# SectionC_BreakOut.net
KiCad netlist of a schematic drawn in Altium Designer
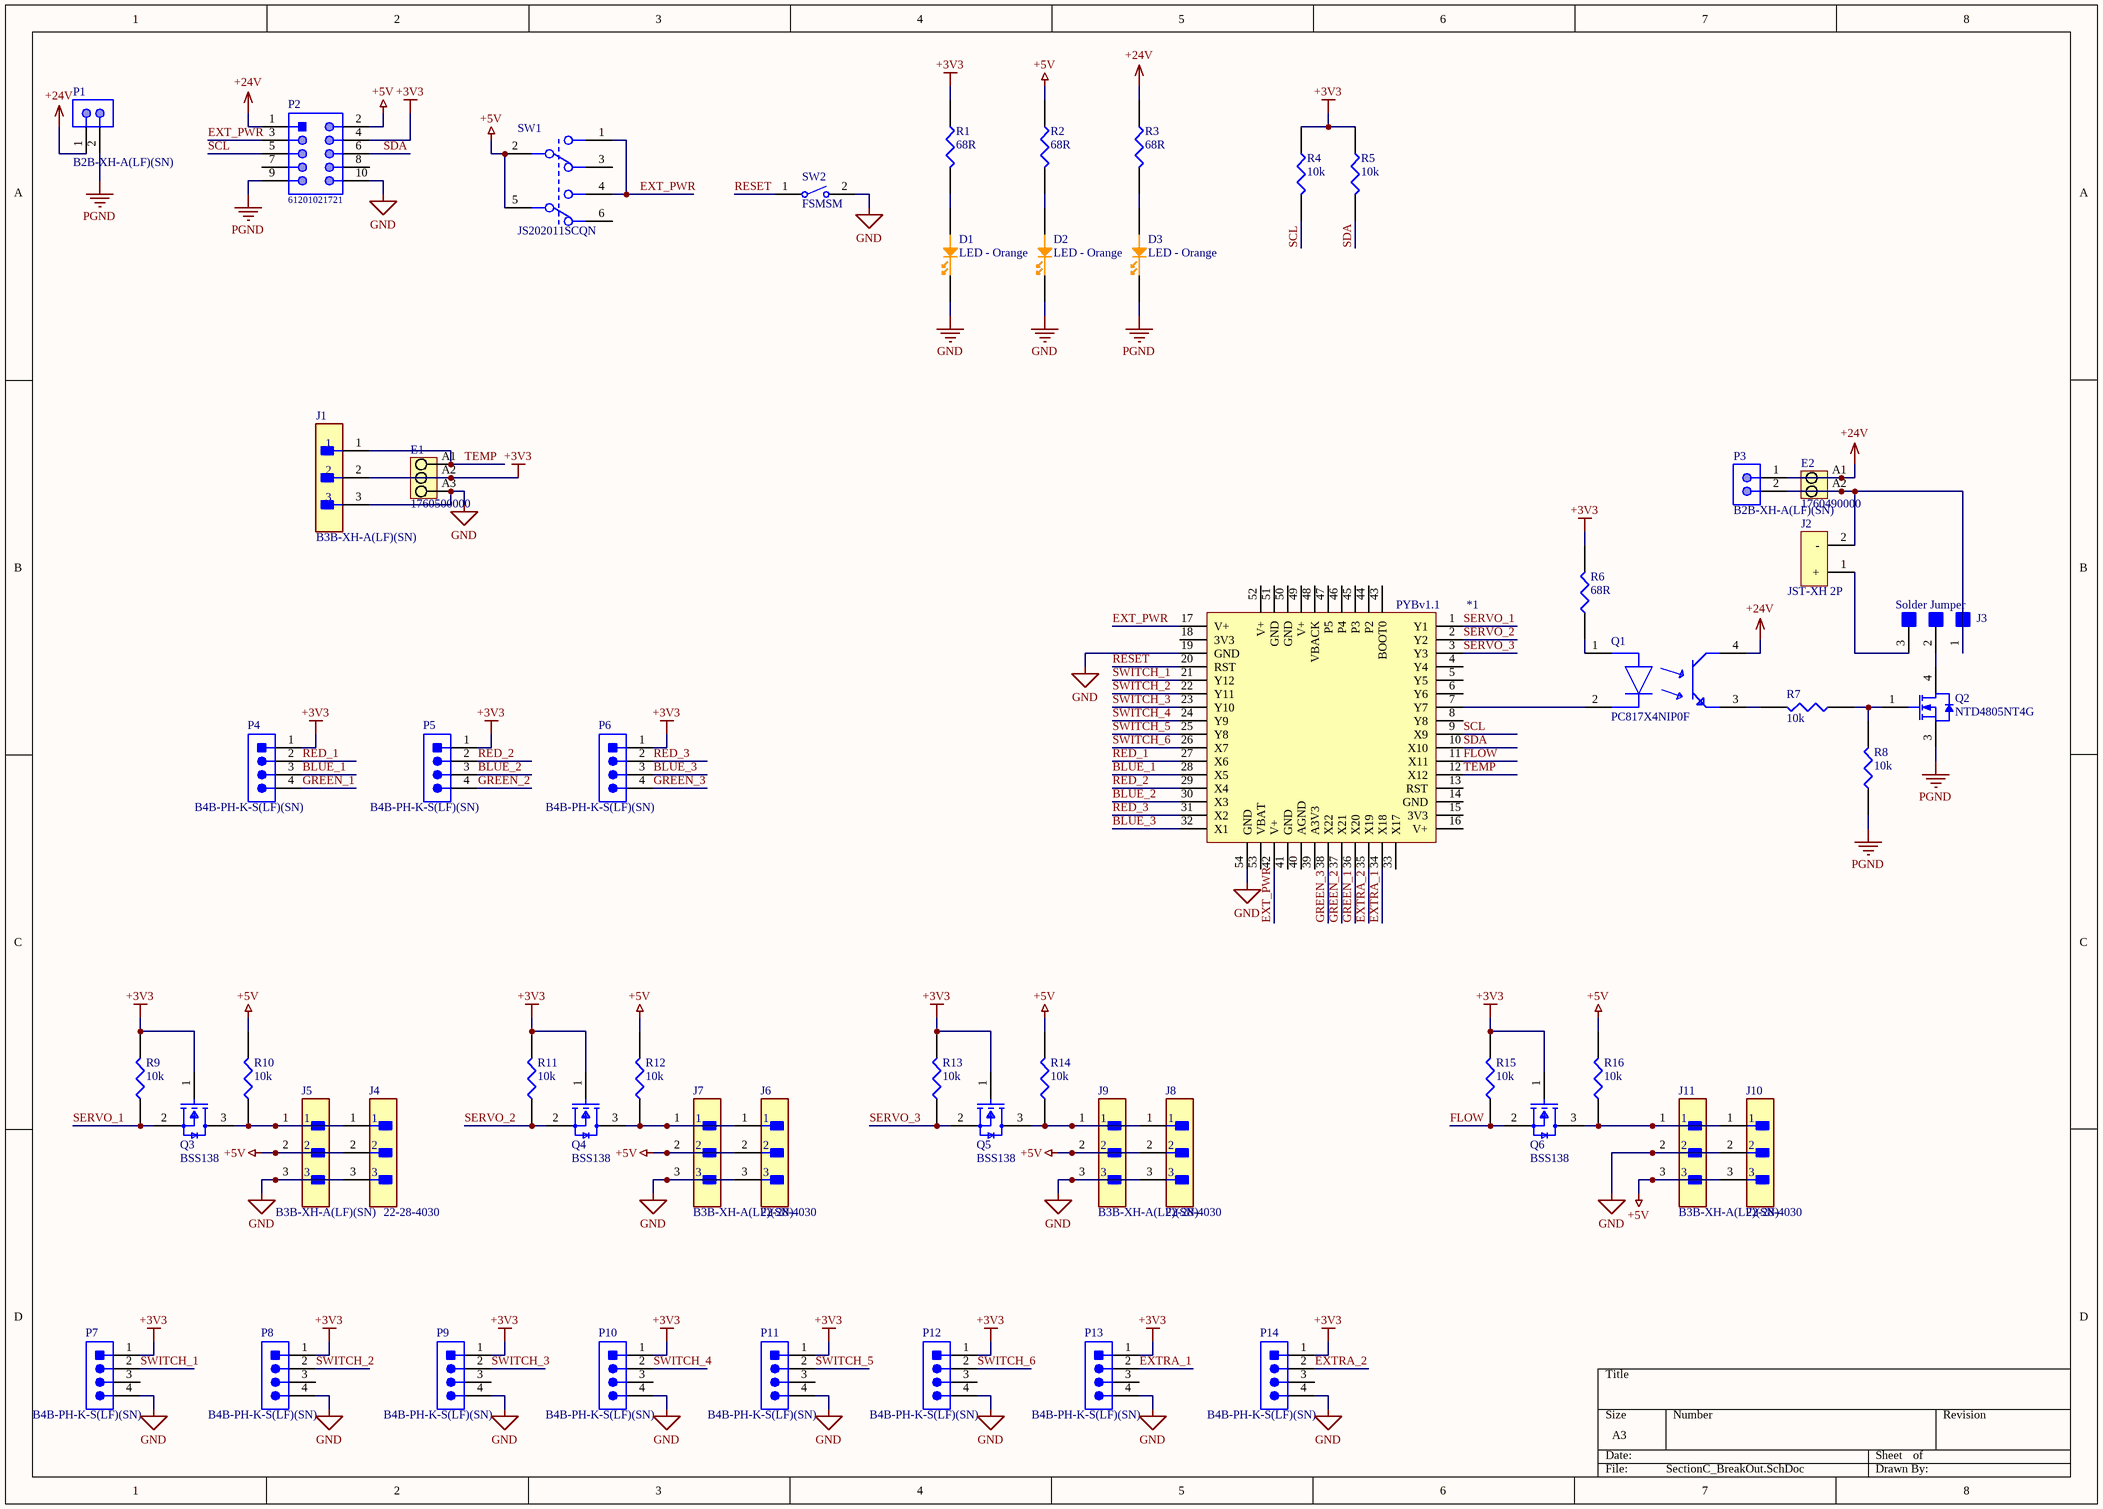
[diagram p0: SectionC_BreakOut.SchDoc]

(export (version "E")
  (design (tool "Eeschema 10.0.6"))
  (components
    (comp (ref "*1")
      (value "PYBv1.1")
      (footprint "PYBv1.1")
      (libsource (lib "SectionC_BreakOut") (part "PYBv1.1"))
    )
    (comp (ref "D1")
      (value "LED - Orange")
      (footprint "LED0603-Orange")
      (description "LED ORANGE CLEAR SMD")
      (fields
        (field (name "MANUFACTURER") "Vishay Lite-On")
        (field (name "MANUFACTURER PART NUMBER") "LTST-C191KFKT")
      )
      (libsource (lib "Limit_Switch_RGB") (part "LTST-C191KFKT"))
    )
    (comp (ref "D2")
      (value "LED - Orange")
      (footprint "LED0603-Orange")
      (description "LED ORANGE CLEAR SMD")
      (fields
        (field (name "MANUFACTURER") "Vishay Lite-On")
        (field (name "MANUFACTURER PART NUMBER") "LTST-C191KFKT")
      )
      (libsource (lib "Limit_Switch_RGB") (part "LTST-C191KFKT"))
    )
    (comp (ref "D3")
      (value "LED - Orange")
      (footprint "LED0603-Orange")
      (description "LED ORANGE CLEAR SMD")
      (fields
        (field (name "MANUFACTURER") "Vishay Lite-On")
        (field (name "MANUFACTURER PART NUMBER") "LTST-C191KFKT")
      )
      (libsource (lib "Limit_Switch_RGB") (part "LTST-C191KFKT"))
    )
    (comp (ref "E1")
      (value "1760500000")
      (footprint "PM_5_08_90_03")
      (description "OMNIMATE Signal - series PM")
      (fields (field (name "MANUFACTURER") "Weidmueller"))
      (libsource (lib "Altium Content Vault") (part "Terminal_03_1x03"))
    )
    (comp (ref "E2")
      (value "1760490000")
      (footprint "PM_5_08_90_02")
      (description "OMNIMATE Signal - series PM")
      (fields (field (name "MANUFACTURER") "Weidmueller"))
      (libsource (lib "Altium Content Vault") (part "Terminal_02_1x02"))
    )
    (comp (ref "J1")
      (value "B3B-XH-A(LF)(SN)")
      (footprint "FP-B3B-XH-A_LF_SN-MFG")
      (description "CONN HEADER VERT 3POS 2.5MM")
      (fields
        (field (name "OCTOPART") "https://octopart.com/b3b-xh-a%28lf%29%28sn%29-jst-3990185")
        (field (name "MANUFACTURER") "JST")
      )
      (libsource (lib "") (part "0d3f023dd272f625e17a2be33dea85f_1"))
    )
    (comp (ref "J2")
      (value "JST-XH 2P")
      (footprint "JST-XH 2P")
      (description "JST-XH 2 POS 2.5mm Solder ST Thru-Hole Box")
      (fields
        (field (name "MANUFACTURER") "JST")
        (field (name "MANUFACTURER PART NUMBER") "B2B-XH-A(LF)(SN)")
      )
      (libsource (lib "SectionE_BreakOut") (part "B2B-XH-A(LF)(SN)"))
    )
    (comp (ref "J3")
      (value "Solder Jumper")
      (footprint "Solder Jumper")
      (libsource (lib "SectionE_BreakOut") (part "Solder Jumper"))
    )
    (comp (ref "J4")
      (value "22-28-4030")
      (footprint "FP-22-28-4030-MFG")
      (description "CONN HEADER VERT 3POS 2.54MM")
      (fields
        (field (name "OCTOPART") "https://octopart.com/0022284030-molex-10476094")
        (field (name "MANUFACTURER") "Molex")
      )
      (libsource (lib "Altium Content Vault") (part "0d3f023dd272f625e17a2be33dea85f"))
    )
    (comp (ref "J5")
      (value "B3B-XH-A(LF)(SN)")
      (footprint "FP-B3B-XH-A_LF_SN-MFG")
      (description "CONN HEADER VERT 3POS 2.5MM")
      (fields
        (field (name "OCTOPART") "https://octopart.com/b3b-xh-a%28lf%29%28sn%29-jst-3990185")
        (field (name "MANUFACTURER") "JST")
      )
      (libsource (lib "Altium Content Vault") (part "0d3f023dd272f625e17a2be33dea85f"))
    )
    (comp (ref "J6")
      (value "22-28-4030")
      (footprint "FP-22-28-4030-MFG")
      (description "CONN HEADER VERT 3POS 2.54MM")
      (fields
        (field (name "OCTOPART") "https://octopart.com/0022284030-molex-10476094")
        (field (name "MANUFACTURER") "Molex")
      )
      (libsource (lib "Altium Content Vault") (part "0d3f023dd272f625e17a2be33dea85f"))
    )
    (comp (ref "J7")
      (value "B3B-XH-A(LF)(SN)")
      (footprint "FP-B3B-XH-A_LF_SN-MFG")
      (description "CONN HEADER VERT 3POS 2.5MM")
      (fields
        (field (name "OCTOPART") "https://octopart.com/b3b-xh-a%28lf%29%28sn%29-jst-3990185")
        (field (name "MANUFACTURER") "JST")
      )
      (libsource (lib "Altium Content Vault") (part "0d3f023dd272f625e17a2be33dea85f"))
    )
    (comp (ref "J8")
      (value "22-28-4030")
      (footprint "FP-22-28-4030-MFG")
      (description "CONN HEADER VERT 3POS 2.54MM")
      (fields
        (field (name "OCTOPART") "https://octopart.com/0022284030-molex-10476094")
        (field (name "MANUFACTURER") "Molex")
      )
      (libsource (lib "Altium Content Vault") (part "0d3f023dd272f625e17a2be33dea85f"))
    )
    (comp (ref "J9")
      (value "B3B-XH-A(LF)(SN)")
      (footprint "FP-B3B-XH-A_LF_SN-MFG")
      (description "CONN HEADER VERT 3POS 2.5MM")
      (fields
        (field (name "OCTOPART") "https://octopart.com/b3b-xh-a%28lf%29%28sn%29-jst-3990185")
        (field (name "MANUFACTURER") "JST")
      )
      (libsource (lib "Altium Content Vault") (part "0d3f023dd272f625e17a2be33dea85f"))
    )
    (comp (ref "J10")
      (value "22-28-4030")
      (footprint "FP-22-28-4030-MFG")
      (description "CONN HEADER VERT 3POS 2.54MM")
      (fields
        (field (name "OCTOPART") "https://octopart.com/0022284030-molex-10476094")
        (field (name "MANUFACTURER") "Molex")
      )
      (libsource (lib "Altium Content Vault") (part "0d3f023dd272f625e17a2be33dea85f"))
    )
    (comp (ref "J11")
      (value "B3B-XH-A(LF)(SN)")
      (footprint "FP-B3B-XH-A_LF_SN-MFG")
      (description "CONN HEADER VERT 3POS 2.5MM")
      (fields
        (field (name "OCTOPART") "https://octopart.com/b3b-xh-a%28lf%29%28sn%29-jst-3990185")
        (field (name "MANUFACTURER") "JST")
      )
      (libsource (lib "Altium Content Vault") (part "0d3f023dd272f625e17a2be33dea85f"))
    )
    (comp (ref "P1")
      (value "B2B-XH-A(LF)(SN)")
      (footprint "JST-B2B-XH-A_V")
      (fields (field (name "MANUFACTURER") "JST"))
      (libsource (lib "Altium Content Vault") (part "CN-1P-M-R2"))
    )
    (comp (ref "P2")
      (value "61201021721")
      (footprint "61201021721")
      (description "Male Box Header WR-BHD, THT, Angled, pitch 2.54 mm, 10 pins")
      (fields (field (name "MANUFACTURER") "Wurth Elektronik") (field (name "PUBLISHER") "WurthElektronik"))
      (libsource (lib "Altium Content Vault") (part "WE-CN-2P-M-R10"))
    )
    (comp (ref "P3")
      (value "B2B-XH-A(LF)(SN)")
      (footprint "JST-B2B-XH-A_V")
      (fields (field (name "MANUFACTURER") "JST"))
      (libsource (lib "") (part "CN-1P-M-R2_1"))
    )
    (comp (ref "P4")
      (value "B4B-PH-K-S(LF)(SN)")
      (footprint "JST-B4B-PH-K-S_V")
      (fields (field (name "MANUFACTURER") "JST"))
      (libsource (lib "Altium Content Vault") (part "CN-1P-M-R4"))
    )
    (comp (ref "P5")
      (value "B4B-PH-K-S(LF)(SN)")
      (footprint "JST-B4B-PH-K-S_V")
      (fields (field (name "MANUFACTURER") "JST"))
      (libsource (lib "Altium Content Vault") (part "CN-1P-M-R4"))
    )
    (comp (ref "P6")
      (value "B4B-PH-K-S(LF)(SN)")
      (footprint "JST-B4B-PH-K-S_V")
      (fields (field (name "MANUFACTURER") "JST"))
      (libsource (lib "Altium Content Vault") (part "CN-1P-M-R4"))
    )
    (comp (ref "P7")
      (value "B4B-PH-K-S(LF)(SN)")
      (footprint "JST-B4B-PH-K-S_V")
      (fields (field (name "MANUFACTURER") "JST"))
      (libsource (lib "Altium Content Vault") (part "CN-1P-M-R4"))
    )
    (comp (ref "P8")
      (value "B4B-PH-K-S(LF)(SN)")
      (footprint "JST-B4B-PH-K-S_V")
      (fields (field (name "MANUFACTURER") "JST"))
      (libsource (lib "Altium Content Vault") (part "CN-1P-M-R4"))
    )
    (comp (ref "P9")
      (value "B4B-PH-K-S(LF)(SN)")
      (footprint "JST-B4B-PH-K-S_V")
      (fields (field (name "MANUFACTURER") "JST"))
      (libsource (lib "Altium Content Vault") (part "CN-1P-M-R4"))
    )
    (comp (ref "P10")
      (value "B4B-PH-K-S(LF)(SN)")
      (footprint "JST-B4B-PH-K-S_V")
      (fields (field (name "MANUFACTURER") "JST"))
      (libsource (lib "Altium Content Vault") (part "CN-1P-M-R4"))
    )
    (comp (ref "P11")
      (value "B4B-PH-K-S(LF)(SN)")
      (footprint "JST-B4B-PH-K-S_V")
      (fields (field (name "MANUFACTURER") "JST"))
      (libsource (lib "Altium Content Vault") (part "CN-1P-M-R4"))
    )
    (comp (ref "P12")
      (value "B4B-PH-K-S(LF)(SN)")
      (footprint "JST-B4B-PH-K-S_V")
      (fields (field (name "MANUFACTURER") "JST"))
      (libsource (lib "Altium Content Vault") (part "CN-1P-M-R4"))
    )
    (comp (ref "P13")
      (value "B4B-PH-K-S(LF)(SN)")
      (footprint "JST-B4B-PH-K-S_V")
      (fields (field (name "MANUFACTURER") "JST"))
      (libsource (lib "Altium Content Vault") (part "CN-1P-M-R4"))
    )
    (comp (ref "P14")
      (value "B4B-PH-K-S(LF)(SN)")
      (footprint "JST-B4B-PH-K-S_V")
      (fields (field (name "MANUFACTURER") "JST"))
      (libsource (lib "Altium Content Vault") (part "CN-1P-M-R4"))
    )
    (comp (ref "Q1")
      (value "PC817X4NIP0F")
      (footprint "FP-PC817X4NIP0F-MFG")
      (description "OPTOISOLATOR 5KV TRANS 4SMD")
      (fields
        (field (name "OCTOPART") "https://octopart.com/pc817x4nip0f-sharp-20650453")
        (field (name "MANUFACTURER") "Sharp")
      )
      (libsource (lib "Altium Content Vault") (part "8ff5844b63c0dea0057760e9ee25456"))
    )
    (comp (ref "Q2")
      (value "NTD4805NT4G")
      (footprint "ONSC-DPAK-3-369AA-01_V")
      (description "Power MOSFET, 30 V, 88 A, Single N-Channel, 3-Pin DPAK, Pb-Free, Tape and Reel")
      (fields (field (name "MANUFACTURER") "On Semiconductor"))
      (libsource (lib "Altium Content Vault") (part "ONSC-NMOS-G1S3D4-3_B"))
    )
    (comp (ref "Q3")
      (value "BSS138")
      (footprint "FP-318-08-IPC_B")
      (description "MOSFET N-CH 50V 220MA SOT-23")
      (libsource (lib "Altium Content Vault") (part "3b9c635fedb024a5347a57b145af9cc"))
    )
    (comp (ref "Q4")
      (value "BSS138")
      (footprint "FP-318-08-IPC_B")
      (description "MOSFET N-CH 50V 220MA SOT-23")
      (libsource (lib "Altium Content Vault") (part "3b9c635fedb024a5347a57b145af9cc"))
    )
    (comp (ref "Q5")
      (value "BSS138")
      (footprint "FP-318-08-IPC_B")
      (description "MOSFET N-CH 50V 220MA SOT-23")
      (libsource (lib "Altium Content Vault") (part "3b9c635fedb024a5347a57b145af9cc"))
    )
    (comp (ref "Q6")
      (value "BSS138")
      (footprint "FP-318-08-IPC_B")
      (description "MOSFET N-CH 50V 220MA SOT-23")
      (libsource (lib "Altium Content Vault") (part "3b9c635fedb024a5347a57b145af9cc"))
    )
    (comp (ref "R1")
      (value "68R")
      (footprint "68R 0603")
      (description "CRGP 0603 68R 1%")
      (fields
        (field (name "MANUFACTURER") "TE Connectivity")
        (field (name "MANUFACTURER PART NUMBER") "CRGP0603F68R")
      )
      (libsource (lib "Limit_Switch_RGB") (part "CRGP0603F68R"))
    )
    (comp (ref "R2")
      (value "68R")
      (footprint "68R 0603")
      (description "CRGP 0603 68R 1%")
      (fields
        (field (name "MANUFACTURER") "TE Connectivity")
        (field (name "MANUFACTURER PART NUMBER") "CRGP0603F68R")
      )
      (libsource (lib "Limit_Switch_RGB") (part "CRGP0603F68R"))
    )
    (comp (ref "R3")
      (value "68R")
      (footprint "68R 0603")
      (description "CRGP 0603 68R 1%")
      (fields
        (field (name "MANUFACTURER") "TE Connectivity")
        (field (name "MANUFACTURER PART NUMBER") "CRGP0603F68R")
      )
      (libsource (lib "Limit_Switch_RGB") (part "CRGP0603F68R"))
    )
    (comp (ref "R4")
      (value "10k")
      (footprint "10k R0603")
      (description "RES 10.0K OHM 1/10W 1% 0603")
      (fields
        (field (name "MANUFACTURER") "TE Connectivity")
        (field (name "MANUFACTURER PART NUMBER") "CRG0603F10K/10")
      )
      (libsource (lib "Limit_Switch_RGB") (part "CRG0603F10K/10"))
    )
    (comp (ref "R5")
      (value "10k")
      (footprint "10k R0603")
      (description "RES 10.0K OHM 1/10W 1% 0603")
      (fields
        (field (name "MANUFACTURER") "TE Connectivity")
        (field (name "MANUFACTURER PART NUMBER") "CRG0603F10K/10")
      )
      (libsource (lib "Limit_Switch_RGB") (part "CRG0603F10K/10"))
    )
    (comp (ref "R6")
      (value "68R")
      (footprint "68R 0603")
      (description "CRGP 0603 68R 1%")
      (fields
        (field (name "MANUFACTURER") "TE Connectivity")
        (field (name "MANUFACTURER PART NUMBER") "CRGP0603F68R")
      )
      (libsource (lib "Limit_Switch_RGB") (part "CRGP0603F68R"))
    )
    (comp (ref "R7")
      (value "10k")
      (footprint "10k R0603")
      (description "RES 10.0K OHM 1/10W 1% 0603")
      (fields
        (field (name "MANUFACTURER") "TE Connectivity")
        (field (name "MANUFACTURER PART NUMBER") "CRG0603F10K/10")
      )
      (libsource (lib "Limit_Switch_RGB") (part "CRG0603F10K/10"))
    )
    (comp (ref "R8")
      (value "10k")
      (footprint "10k R0603")
      (description "RES 10.0K OHM 1/10W 1% 0603")
      (fields
        (field (name "MANUFACTURER") "TE Connectivity")
        (field (name "MANUFACTURER PART NUMBER") "CRG0603F10K/10")
      )
      (libsource (lib "Limit_Switch_RGB") (part "CRG0603F10K/10"))
    )
    (comp (ref "R9")
      (value "10k")
      (footprint "10k R0603")
      (description "RES 10.0K OHM 1/10W 1% 0603")
      (fields
        (field (name "MANUFACTURER") "TE Connectivity")
        (field (name "MANUFACTURER PART NUMBER") "CRG0603F10K/10")
      )
      (libsource (lib "Limit_Switch_RGB") (part "CRG0603F10K/10"))
    )
    (comp (ref "R10")
      (value "10k")
      (footprint "10k R0603")
      (description "RES 10.0K OHM 1/10W 1% 0603")
      (fields
        (field (name "MANUFACTURER") "TE Connectivity")
        (field (name "MANUFACTURER PART NUMBER") "CRG0603F10K/10")
      )
      (libsource (lib "Limit_Switch_RGB") (part "CRG0603F10K/10"))
    )
    (comp (ref "R11")
      (value "10k")
      (footprint "10k R0603")
      (description "RES 10.0K OHM 1/10W 1% 0603")
      (fields
        (field (name "MANUFACTURER") "TE Connectivity")
        (field (name "MANUFACTURER PART NUMBER") "CRG0603F10K/10")
      )
      (libsource (lib "Limit_Switch_RGB") (part "CRG0603F10K/10"))
    )
    (comp (ref "R12")
      (value "10k")
      (footprint "10k R0603")
      (description "RES 10.0K OHM 1/10W 1% 0603")
      (fields
        (field (name "MANUFACTURER") "TE Connectivity")
        (field (name "MANUFACTURER PART NUMBER") "CRG0603F10K/10")
      )
      (libsource (lib "Limit_Switch_RGB") (part "CRG0603F10K/10"))
    )
    (comp (ref "R13")
      (value "10k")
      (footprint "10k R0603")
      (description "RES 10.0K OHM 1/10W 1% 0603")
      (fields
        (field (name "MANUFACTURER") "TE Connectivity")
        (field (name "MANUFACTURER PART NUMBER") "CRG0603F10K/10")
      )
      (libsource (lib "Limit_Switch_RGB") (part "CRG0603F10K/10"))
    )
    (comp (ref "R14")
      (value "10k")
      (footprint "10k R0603")
      (description "RES 10.0K OHM 1/10W 1% 0603")
      (fields
        (field (name "MANUFACTURER") "TE Connectivity")
        (field (name "MANUFACTURER PART NUMBER") "CRG0603F10K/10")
      )
      (libsource (lib "Limit_Switch_RGB") (part "CRG0603F10K/10"))
    )
    (comp (ref "R15")
      (value "10k")
      (footprint "10k R0603")
      (description "RES 10.0K OHM 1/10W 1% 0603")
      (fields
        (field (name "MANUFACTURER") "TE Connectivity")
        (field (name "MANUFACTURER PART NUMBER") "CRG0603F10K/10")
      )
      (libsource (lib "Limit_Switch_RGB") (part "CRG0603F10K/10"))
    )
    (comp (ref "R16")
      (value "10k")
      (footprint "10k R0603")
      (description "RES 10.0K OHM 1/10W 1% 0603")
      (fields
        (field (name "MANUFACTURER") "TE Connectivity")
        (field (name "MANUFACTURER PART NUMBER") "CRG0603F10K/10")
      )
      (libsource (lib "Limit_Switch_RGB") (part "CRG0603F10K/10"))
    )
    (comp (ref "SW1")
      (value "JS202011SCQN")
      (footprint "FP-JS202011SCQN-MFG")
      (description "SWITCH SLIDE DPDT 300MA 6V")
      (libsource (lib "Altium Content Vault") (part "ac99ea1af431c19115f5225061c5c88"))
    )
    (comp (ref "SW2")
      (value "FSMSM")
      (footprint "TECO-FSMSM-2_V")
      (description "FSMSM Push Button Switch, 50 mA, -35 to 85 degC, 2-Pin SMD, RoHS, Bulk")
      (fields (field (name "MANUFACTURER") "TE Connectivity"))
      (libsource (lib "Altium Content Vault") (part "SW-SPST-2_C"))
    )
  )
  (nets
    (net (code "1") (name "+3V3") (class "Default")
      (node (ref "E1") (pin "A2") (pinfunction "A2_A2") (pintype "passive"))
      (node (ref "J1") (pin "2") (pinfunction "2_2") (pintype "passive"))
      (node (ref "P10") (pin "1") (pinfunction "1_1") (pintype "passive"))
      (node (ref "P11") (pin "1") (pinfunction "1_1") (pintype "passive"))
      (node (ref "P12") (pin "1") (pinfunction "1_1") (pintype "passive"))
      (node (ref "P13") (pin "1") (pinfunction "1_1") (pintype "passive"))
      (node (ref "P14") (pin "1") (pinfunction "1_1") (pintype "passive"))
      (node (ref "P2") (pin "4") (pinfunction "4_4") (pintype "passive"))
      (node (ref "P4") (pin "1") (pinfunction "1_1") (pintype "passive"))
      (node (ref "P5") (pin "1") (pinfunction "1_1") (pintype "passive"))
      (node (ref "P6") (pin "1") (pinfunction "1_1") (pintype "passive"))
      (node (ref "P7") (pin "1") (pinfunction "1_1") (pintype "passive"))
      (node (ref "P8") (pin "1") (pinfunction "1_1") (pintype "passive"))
      (node (ref "P9") (pin "1") (pinfunction "1_1") (pintype "passive"))
      (node (ref "Q3") (pin "1") (pinfunction "G_1") (pintype "passive"))
      (node (ref "Q4") (pin "1") (pinfunction "G_1") (pintype "passive"))
      (node (ref "Q5") (pin "1") (pinfunction "G_1") (pintype "passive"))
      (node (ref "Q6") (pin "1") (pinfunction "G_1") (pintype "passive"))
      (node (ref "R1") (pin "1") (pinfunction "1_1") (pintype "passive"))
      (node (ref "R11") (pin "2") (pinfunction "2_2") (pintype "passive"))
      (node (ref "R13") (pin "2") (pinfunction "2_2") (pintype "passive"))
      (node (ref "R15") (pin "2") (pinfunction "2_2") (pintype "passive"))
      (node (ref "R4") (pin "1") (pinfunction "1_1") (pintype "passive"))
      (node (ref "R5") (pin "1") (pinfunction "1_1") (pintype "passive"))
      (node (ref "R6") (pin "2") (pinfunction "2_2") (pintype "passive"))
      (node (ref "R9") (pin "2") (pinfunction "2_2") (pintype "passive"))
    )
    (net (code "2") (name "+5V") (class "Default")
      (node (ref "J10") (pin "3") (pinfunction "3_3") (pintype "passive"))
      (node (ref "J11") (pin "3") (pinfunction "3_3") (pintype "passive"))
      (node (ref "J4") (pin "2") (pinfunction "2_2") (pintype "passive"))
      (node (ref "J5") (pin "2") (pinfunction "2_2") (pintype "passive"))
      (node (ref "J6") (pin "2") (pinfunction "2_2") (pintype "passive"))
      (node (ref "J7") (pin "2") (pinfunction "2_2") (pintype "passive"))
      (node (ref "J8") (pin "2") (pinfunction "2_2") (pintype "passive"))
      (node (ref "J9") (pin "2") (pinfunction "2_2") (pintype "passive"))
      (node (ref "P2") (pin "2") (pinfunction "2_2") (pintype "passive"))
      (node (ref "R10") (pin "2") (pinfunction "2_2") (pintype "passive"))
      (node (ref "R12") (pin "2") (pinfunction "2_2") (pintype "passive"))
      (node (ref "R14") (pin "2") (pinfunction "2_2") (pintype "passive"))
      (node (ref "R16") (pin "2") (pinfunction "2_2") (pintype "passive"))
      (node (ref "R2") (pin "1") (pinfunction "1_1") (pintype "passive"))
      (node (ref "SW1") (pin "2") (pinfunction "2_2") (pintype "passive"))
      (node (ref "SW1") (pin "5") (pinfunction "5_5") (pintype "passive"))
    )
    (net (code "3") (name "+24V") (class "Default")
      (node (ref "E2") (pin "A1") (pinfunction "A1_A1") (pintype "passive"))
      (node (ref "P1") (pin "1") (pinfunction "1_1") (pintype "passive"))
      (node (ref "P2") (pin "1") (pinfunction "1_1") (pintype "passive"))
      (node (ref "P3") (pin "1") (pinfunction "1_1") (pintype "passive"))
      (node (ref "Q1") (pin "4") (pinfunction "C_4") (pintype "passive"))
      (node (ref "R3") (pin "1") (pinfunction "1_1") (pintype "passive"))
    )
    (net (code "4") (name "/BLUE_1") (class "Default")
      (node (ref "*1") (pin "28") (pinfunction "X5_28") (pintype "passive"))
      (node (ref "P4") (pin "3") (pinfunction "3_3") (pintype "passive"))
    )
    (net (code "5") (name "/BLUE_2") (class "Default")
      (node (ref "*1") (pin "30") (pinfunction "X3_30") (pintype "passive"))
      (node (ref "P5") (pin "3") (pinfunction "3_3") (pintype "passive"))
    )
    (net (code "6") (name "/BLUE_3") (class "Default")
      (node (ref "*1") (pin "32") (pinfunction "X1_32") (pintype "passive"))
      (node (ref "P6") (pin "3") (pinfunction "3_3") (pintype "passive"))
    )
    (net (code "7") (name "/EXTRA_1") (class "Default")
      (node (ref "*1") (pin "34") (pinfunction "X18_34") (pintype "passive"))
      (node (ref "P13") (pin "2") (pinfunction "2_2") (pintype "passive"))
    )
    (net (code "8") (name "/EXTRA_2") (class "Default")
      (node (ref "*1") (pin "35") (pinfunction "X19_35") (pintype "passive"))
      (node (ref "P14") (pin "2") (pinfunction "2_2") (pintype "passive"))
    )
    (net (code "9") (name "/EXT_PWR") (class "Default")
      (node (ref "*1") (pin "17") (pinfunction "V+_17") (pintype "passive"))
      (node (ref "*1") (pin "42") (pinfunction "V+_42") (pintype "passive"))
      (node (ref "P2") (pin "3") (pinfunction "3_3") (pintype "passive"))
      (node (ref "SW1") (pin "1") (pinfunction "1_1") (pintype "passive"))
      (node (ref "SW1") (pin "4") (pinfunction "4_4") (pintype "passive"))
    )
    (net (code "10") (name "/FLOW") (class "Default")
      (node (ref "*1") (pin "11") (pinfunction "X11_11") (pintype "passive"))
      (node (ref "Q6") (pin "2") (pinfunction "S_2") (pintype "passive"))
      (node (ref "R15") (pin "1") (pinfunction "1_1") (pintype "passive"))
    )
    (net (code "11") (name "/GREEN_1") (class "Default")
      (node (ref "*1") (pin "36") (pinfunction "X20_36") (pintype "passive"))
      (node (ref "P4") (pin "4") (pinfunction "4_4") (pintype "passive"))
    )
    (net (code "12") (name "/GREEN_2") (class "Default")
      (node (ref "*1") (pin "37") (pinfunction "X21_37") (pintype "passive"))
      (node (ref "P5") (pin "4") (pinfunction "4_4") (pintype "passive"))
    )
    (net (code "13") (name "/GREEN_3") (class "Default")
      (node (ref "*1") (pin "38") (pinfunction "X22_38") (pintype "passive"))
      (node (ref "P6") (pin "4") (pinfunction "4_4") (pintype "passive"))
    )
    (net (code "14") (name "/RED_1") (class "Default")
      (node (ref "*1") (pin "27") (pinfunction "X6_27") (pintype "passive"))
      (node (ref "P4") (pin "2") (pinfunction "2_2") (pintype "passive"))
    )
    (net (code "15") (name "/RED_2") (class "Default")
      (node (ref "*1") (pin "29") (pinfunction "X4_29") (pintype "passive"))
      (node (ref "P5") (pin "2") (pinfunction "2_2") (pintype "passive"))
    )
    (net (code "16") (name "/RED_3") (class "Default")
      (node (ref "*1") (pin "31") (pinfunction "X2_31") (pintype "passive"))
      (node (ref "P6") (pin "2") (pinfunction "2_2") (pintype "passive"))
    )
    (net (code "17") (name "/RESET") (class "Default")
      (node (ref "*1") (pin "20") (pinfunction "RST_20") (pintype "passive"))
      (node (ref "SW2") (pin "1") (pinfunction "1_1") (pintype "passive"))
    )
    (net (code "18") (name "/SCL") (class "Default")
      (node (ref "*1") (pin "9") (pinfunction "X9_9") (pintype "passive"))
      (node (ref "P2") (pin "5") (pinfunction "5_5") (pintype "passive"))
      (node (ref "R4") (pin "2") (pinfunction "2_2") (pintype "passive"))
    )
    (net (code "19") (name "/SDA") (class "Default")
      (node (ref "*1") (pin "10") (pinfunction "X10_10") (pintype "passive"))
      (node (ref "P2") (pin "6") (pinfunction "6_6") (pintype "passive"))
      (node (ref "R5") (pin "2") (pinfunction "2_2") (pintype "passive"))
    )
    (net (code "20") (name "/SERVO_1") (class "Default")
      (node (ref "*1") (pin "1") (pinfunction "Y1_1") (pintype "passive"))
      (node (ref "Q3") (pin "2") (pinfunction "S_2") (pintype "passive"))
      (node (ref "R9") (pin "1") (pinfunction "1_1") (pintype "passive"))
    )
    (net (code "21") (name "/SERVO_2") (class "Default")
      (node (ref "*1") (pin "2") (pinfunction "Y2_2") (pintype "passive"))
      (node (ref "Q4") (pin "2") (pinfunction "S_2") (pintype "passive"))
      (node (ref "R11") (pin "1") (pinfunction "1_1") (pintype "passive"))
    )
    (net (code "22") (name "/SERVO_3") (class "Default")
      (node (ref "*1") (pin "3") (pinfunction "Y3_3") (pintype "passive"))
      (node (ref "Q5") (pin "2") (pinfunction "S_2") (pintype "passive"))
      (node (ref "R13") (pin "1") (pinfunction "1_1") (pintype "passive"))
    )
    (net (code "23") (name "/SWITCH_1") (class "Default")
      (node (ref "*1") (pin "21") (pinfunction "Y12_21") (pintype "passive"))
      (node (ref "P7") (pin "2") (pinfunction "2_2") (pintype "passive"))
    )
    (net (code "24") (name "/SWITCH_2") (class "Default")
      (node (ref "*1") (pin "22") (pinfunction "Y11_22") (pintype "passive"))
      (node (ref "P8") (pin "2") (pinfunction "2_2") (pintype "passive"))
    )
    (net (code "25") (name "/SWITCH_3") (class "Default")
      (node (ref "*1") (pin "23") (pinfunction "Y10_23") (pintype "passive"))
      (node (ref "P9") (pin "2") (pinfunction "2_2") (pintype "passive"))
    )
    (net (code "26") (name "/SWITCH_4") (class "Default")
      (node (ref "*1") (pin "24") (pinfunction "Y9_24") (pintype "passive"))
      (node (ref "P10") (pin "2") (pinfunction "2_2") (pintype "passive"))
    )
    (net (code "27") (name "/SWITCH_5") (class "Default")
      (node (ref "*1") (pin "25") (pinfunction "Y8_25") (pintype "passive"))
      (node (ref "P11") (pin "2") (pinfunction "2_2") (pintype "passive"))
    )
    (net (code "28") (name "/SWITCH_6") (class "Default")
      (node (ref "*1") (pin "26") (pinfunction "X7_26") (pintype "passive"))
      (node (ref "P12") (pin "2") (pinfunction "2_2") (pintype "passive"))
    )
    (net (code "29") (name "/TEMP") (class "Default")
      (node (ref "*1") (pin "12") (pinfunction "X12_12") (pintype "passive"))
      (node (ref "E1") (pin "A1") (pinfunction "A1_A1") (pintype "passive"))
      (node (ref "J1") (pin "1") (pinfunction "1_1") (pintype "passive"))
    )
    (net (code "30") (name "GND") (class "Default")
      (node (ref "*1") (pin "19") (pinfunction "GND_19") (pintype "passive"))
      (node (ref "*1") (pin "54") (pinfunction "GND_54") (pintype "passive"))
      (node (ref "D1") (pin "1") (pinfunction "Cathode_1") (pintype "passive"))
      (node (ref "D2") (pin "1") (pinfunction "Cathode_1") (pintype "passive"))
      (node (ref "E1") (pin "A3") (pinfunction "A3_A3") (pintype "passive"))
      (node (ref "J1") (pin "3") (pinfunction "3_3") (pintype "passive"))
      (node (ref "J10") (pin "2") (pinfunction "2_2") (pintype "passive"))
      (node (ref "J11") (pin "2") (pinfunction "2_2") (pintype "passive"))
      (node (ref "J4") (pin "3") (pinfunction "3_3") (pintype "passive"))
      (node (ref "J5") (pin "3") (pinfunction "3_3") (pintype "passive"))
      (node (ref "J6") (pin "3") (pinfunction "3_3") (pintype "passive"))
      (node (ref "J7") (pin "3") (pinfunction "3_3") (pintype "passive"))
      (node (ref "J8") (pin "3") (pinfunction "3_3") (pintype "passive"))
      (node (ref "J9") (pin "3") (pinfunction "3_3") (pintype "passive"))
      (node (ref "P10") (pin "4") (pinfunction "4_4") (pintype "passive"))
      (node (ref "P11") (pin "4") (pinfunction "4_4") (pintype "passive"))
      (node (ref "P12") (pin "4") (pinfunction "4_4") (pintype "passive"))
      (node (ref "P13") (pin "4") (pinfunction "4_4") (pintype "passive"))
      (node (ref "P14") (pin "4") (pinfunction "4_4") (pintype "passive"))
      (node (ref "P2") (pin "10") (pinfunction "10_10") (pintype "passive"))
      (node (ref "P7") (pin "4") (pinfunction "4_4") (pintype "passive"))
      (node (ref "P8") (pin "4") (pinfunction "4_4") (pintype "passive"))
      (node (ref "P9") (pin "4") (pinfunction "4_4") (pintype "passive"))
      (node (ref "SW2") (pin "2") (pinfunction "2_2") (pintype "passive"))
    )
    (net (code "31") (name "Net-(*1-Y7)") (class "Default")
      (node (ref "*1") (pin "7") (pinfunction "Y7_7") (pintype "passive"))
      (node (ref "Q1") (pin "2") (pinfunction "C_2") (pintype "passive"))
    )
    (net (code "32") (name "Net-(D1-Anode)") (class "Default")
      (node (ref "D1") (pin "2") (pinfunction "Anode_2") (pintype "passive"))
      (node (ref "R1") (pin "2") (pinfunction "2_2") (pintype "passive"))
    )
    (net (code "33") (name "Net-(D2-Anode)") (class "Default")
      (node (ref "D2") (pin "2") (pinfunction "Anode_2") (pintype "passive"))
      (node (ref "R2") (pin "2") (pinfunction "2_2") (pintype "passive"))
    )
    (net (code "34") (name "Net-(D3-Anode)") (class "Default")
      (node (ref "D3") (pin "2") (pinfunction "Anode_2") (pintype "passive"))
      (node (ref "R3") (pin "2") (pinfunction "2_2") (pintype "passive"))
    )
    (net (code "35") (name "Net-(J2-+)") (class "Default")
      (node (ref "J2") (pin "1") (pinfunction "+_1") (pintype "passive"))
      (node (ref "J3") (pin "3") (pinfunction "3_3") (pintype "passive"))
    )
    (net (code "36") (name "Net-(J2--)") (class "Default")
      (node (ref "E2") (pin "A2") (pinfunction "A2_A2") (pintype "passive"))
      (node (ref "J2") (pin "2") (pinfunction "-_2") (pintype "passive"))
      (node (ref "J3") (pin "1") (pinfunction "1_1") (pintype "passive"))
      (node (ref "P3") (pin "2") (pinfunction "2_2") (pintype "passive"))
    )
    (net (code "37") (name "Net-(Q1-A)") (class "Default")
      (node (ref "Q1") (pin "1") (pinfunction "A_1") (pintype "passive"))
      (node (ref "R6") (pin "1") (pinfunction "1_1") (pintype "passive"))
    )
    (net (code "38") (name "Net-(Q1-E)") (class "Default")
      (node (ref "Q1") (pin "3") (pinfunction "E_3") (pintype "passive"))
      (node (ref "R7") (pin "2") (pinfunction "2_2") (pintype "passive"))
    )
    (net (code "39") (name "Net-(Q2-D)") (class "Default")
      (node (ref "J3") (pin "2") (pinfunction "2_2") (pintype "passive"))
      (node (ref "Q2") (pin "4") (pinfunction "D_4") (pintype "passive"))
    )
    (net (code "40") (name "Net-(Q2-G)") (class "Default")
      (node (ref "Q2") (pin "1") (pinfunction "G_1") (pintype "passive"))
      (node (ref "R7") (pin "1") (pinfunction "1_1") (pintype "passive"))
      (node (ref "R8") (pin "2") (pinfunction "2_2") (pintype "passive"))
    )
    (net (code "41") (name "Net-(Q3-D)") (class "Default")
      (node (ref "J4") (pin "1") (pinfunction "1_1") (pintype "passive"))
      (node (ref "J5") (pin "1") (pinfunction "1_1") (pintype "passive"))
      (node (ref "Q3") (pin "3") (pinfunction "D_3") (pintype "passive"))
      (node (ref "R10") (pin "1") (pinfunction "1_1") (pintype "passive"))
    )
    (net (code "42") (name "Net-(Q4-D)") (class "Default")
      (node (ref "J6") (pin "1") (pinfunction "1_1") (pintype "passive"))
      (node (ref "J7") (pin "1") (pinfunction "1_1") (pintype "passive"))
      (node (ref "Q4") (pin "3") (pinfunction "D_3") (pintype "passive"))
      (node (ref "R12") (pin "1") (pinfunction "1_1") (pintype "passive"))
    )
    (net (code "43") (name "Net-(Q5-D)") (class "Default")
      (node (ref "J8") (pin "1") (pinfunction "1_1") (pintype "passive"))
      (node (ref "J9") (pin "1") (pinfunction "1_1") (pintype "passive"))
      (node (ref "Q5") (pin "3") (pinfunction "D_3") (pintype "passive"))
      (node (ref "R14") (pin "1") (pinfunction "1_1") (pintype "passive"))
    )
    (net (code "44") (name "Net-(Q6-D)") (class "Default")
      (node (ref "J10") (pin "1") (pinfunction "1_1") (pintype "passive"))
      (node (ref "J11") (pin "1") (pinfunction "1_1") (pintype "passive"))
      (node (ref "Q6") (pin "3") (pinfunction "D_3") (pintype "passive"))
      (node (ref "R16") (pin "1") (pinfunction "1_1") (pintype "passive"))
    )
    (net (code "45") (name "PGND") (class "Default")
      (node (ref "D3") (pin "1") (pinfunction "Cathode_1") (pintype "passive"))
      (node (ref "P1") (pin "2") (pinfunction "2_2") (pintype "passive"))
      (node (ref "P2") (pin "9") (pinfunction "9_9") (pintype "passive"))
      (node (ref "Q2") (pin "3") (pinfunction "S_3") (pintype "passive"))
      (node (ref "R8") (pin "1") (pinfunction "1_1") (pintype "passive"))
    )
    (net (code "46") (name "unconnected-(*1-3V3-Pad15)") (class "Default")
      (node (ref "*1") (pin "15") (pinfunction "3V3_15") (pintype "passive"))
    )
    (net (code "47") (name "unconnected-(*1-3V3-Pad18)") (class "Default")
      (node (ref "*1") (pin "18") (pinfunction "3V3_18") (pintype "passive"))
    )
    (net (code "48") (name "unconnected-(*1-A3V3-Pad39)") (class "Default")
      (node (ref "*1") (pin "39") (pinfunction "A3V3_39") (pintype "passive"))
    )
    (net (code "49") (name "unconnected-(*1-AGND-Pad40)") (class "Default")
      (node (ref "*1") (pin "40") (pinfunction "AGND_40") (pintype "passive"))
    )
    (net (code "50") (name "unconnected-(*1-BOOT0-Pad43)") (class "Default")
      (node (ref "*1") (pin "43") (pinfunction "BOOT0_43") (pintype "passive"))
    )
    (net (code "51") (name "unconnected-(*1-GND-Pad14)") (class "Default")
      (node (ref "*1") (pin "14") (pinfunction "GND_14") (pintype "passive"))
    )
    (net (code "52") (name "unconnected-(*1-GND-Pad41)") (class "Default")
      (node (ref "*1") (pin "41") (pinfunction "GND_41") (pintype "passive"))
    )
    (net (code "53") (name "unconnected-(*1-GND-Pad50)") (class "Default")
      (node (ref "*1") (pin "50") (pinfunction "GND_50") (pintype "passive"))
    )
    (net (code "54") (name "unconnected-(*1-GND-Pad51)") (class "Default")
      (node (ref "*1") (pin "51") (pinfunction "GND_51") (pintype "passive"))
    )
    (net (code "55") (name "unconnected-(*1-P2-Pad44)") (class "Default")
      (node (ref "*1") (pin "44") (pinfunction "P2_44") (pintype "passive"))
    )
    (net (code "56") (name "unconnected-(*1-P3-Pad45)") (class "Default")
      (node (ref "*1") (pin "45") (pinfunction "P3_45") (pintype "passive"))
    )
    (net (code "57") (name "unconnected-(*1-P4-Pad46)") (class "Default")
      (node (ref "*1") (pin "46") (pinfunction "P4_46") (pintype "passive"))
    )
    (net (code "58") (name "unconnected-(*1-P5-Pad47)") (class "Default")
      (node (ref "*1") (pin "47") (pinfunction "P5_47") (pintype "passive"))
    )
    (net (code "59") (name "unconnected-(*1-RST-Pad13)") (class "Default")
      (node (ref "*1") (pin "13") (pinfunction "RST_13") (pintype "passive"))
    )
    (net (code "60") (name "unconnected-(*1-V+-Pad16)") (class "Default")
      (node (ref "*1") (pin "16") (pinfunction "V+_16") (pintype "passive"))
    )
    (net (code "61") (name "unconnected-(*1-V+-Pad49)") (class "Default")
      (node (ref "*1") (pin "49") (pinfunction "V+_49") (pintype "passive"))
    )
    (net (code "62") (name "unconnected-(*1-V+-Pad52)") (class "Default")
      (node (ref "*1") (pin "52") (pinfunction "V+_52") (pintype "passive"))
    )
    (net (code "63") (name "unconnected-(*1-VBACK-Pad48)") (class "Default")
      (node (ref "*1") (pin "48") (pinfunction "VBACK_48") (pintype "passive"))
    )
    (net (code "64") (name "unconnected-(*1-VBAT-Pad53)") (class "Default")
      (node (ref "*1") (pin "53") (pinfunction "VBAT_53") (pintype "passive"))
    )
    (net (code "65") (name "unconnected-(*1-X17-Pad33)") (class "Default")
      (node (ref "*1") (pin "33") (pinfunction "X17_33") (pintype "passive"))
    )
    (net (code "66") (name "unconnected-(*1-Y4-Pad4)") (class "Default")
      (node (ref "*1") (pin "4") (pinfunction "Y4_4") (pintype "passive"))
    )
    (net (code "67") (name "unconnected-(*1-Y5-Pad5)") (class "Default")
      (node (ref "*1") (pin "5") (pinfunction "Y5_5") (pintype "passive"))
    )
    (net (code "68") (name "unconnected-(*1-Y6-Pad6)") (class "Default")
      (node (ref "*1") (pin "6") (pinfunction "Y6_6") (pintype "passive"))
    )
    (net (code "69") (name "unconnected-(*1-Y8-Pad8)") (class "Default")
      (node (ref "*1") (pin "8") (pinfunction "Y8_8") (pintype "passive"))
    )
    (net (code "70") (name "unconnected-(P2-Pad7)") (class "Default")
      (node (ref "P2") (pin "7") (pinfunction "7_7") (pintype "passive"))
    )
    (net (code "71") (name "unconnected-(P2-Pad8)") (class "Default")
      (node (ref "P2") (pin "8") (pinfunction "8_8") (pintype "passive"))
    )
    (net (code "72") (name "unconnected-(P7-Pad3)") (class "Default")
      (node (ref "P7") (pin "3") (pinfunction "3_3") (pintype "passive"))
    )
    (net (code "73") (name "unconnected-(P8-Pad3)") (class "Default")
      (node (ref "P8") (pin "3") (pinfunction "3_3") (pintype "passive"))
    )
    (net (code "74") (name "unconnected-(P9-Pad3)") (class "Default")
      (node (ref "P9") (pin "3") (pinfunction "3_3") (pintype "passive"))
    )
    (net (code "75") (name "unconnected-(P10-Pad3)") (class "Default")
      (node (ref "P10") (pin "3") (pinfunction "3_3") (pintype "passive"))
    )
    (net (code "76") (name "unconnected-(P11-Pad3)") (class "Default")
      (node (ref "P11") (pin "3") (pinfunction "3_3") (pintype "passive"))
    )
    (net (code "77") (name "unconnected-(P12-Pad3)") (class "Default")
      (node (ref "P12") (pin "3") (pinfunction "3_3") (pintype "passive"))
    )
    (net (code "78") (name "unconnected-(P13-Pad3)") (class "Default")
      (node (ref "P13") (pin "3") (pinfunction "3_3") (pintype "passive"))
    )
    (net (code "79") (name "unconnected-(P14-Pad3)") (class "Default")
      (node (ref "P14") (pin "3") (pinfunction "3_3") (pintype "passive"))
    )
    (net (code "80") (name "unconnected-(SW1-Pad3)") (class "Default")
      (node (ref "SW1") (pin "3") (pinfunction "3_3") (pintype "passive"))
    )
    (net (code "81") (name "unconnected-(SW1-Pad6)") (class "Default")
      (node (ref "SW1") (pin "6") (pinfunction "6_6") (pintype "passive"))
    )
  )
)
